# LB_BIT_1OUT-XL-v03_1_1x.net
KiCad netlist of a schematic drawn in EAGLE
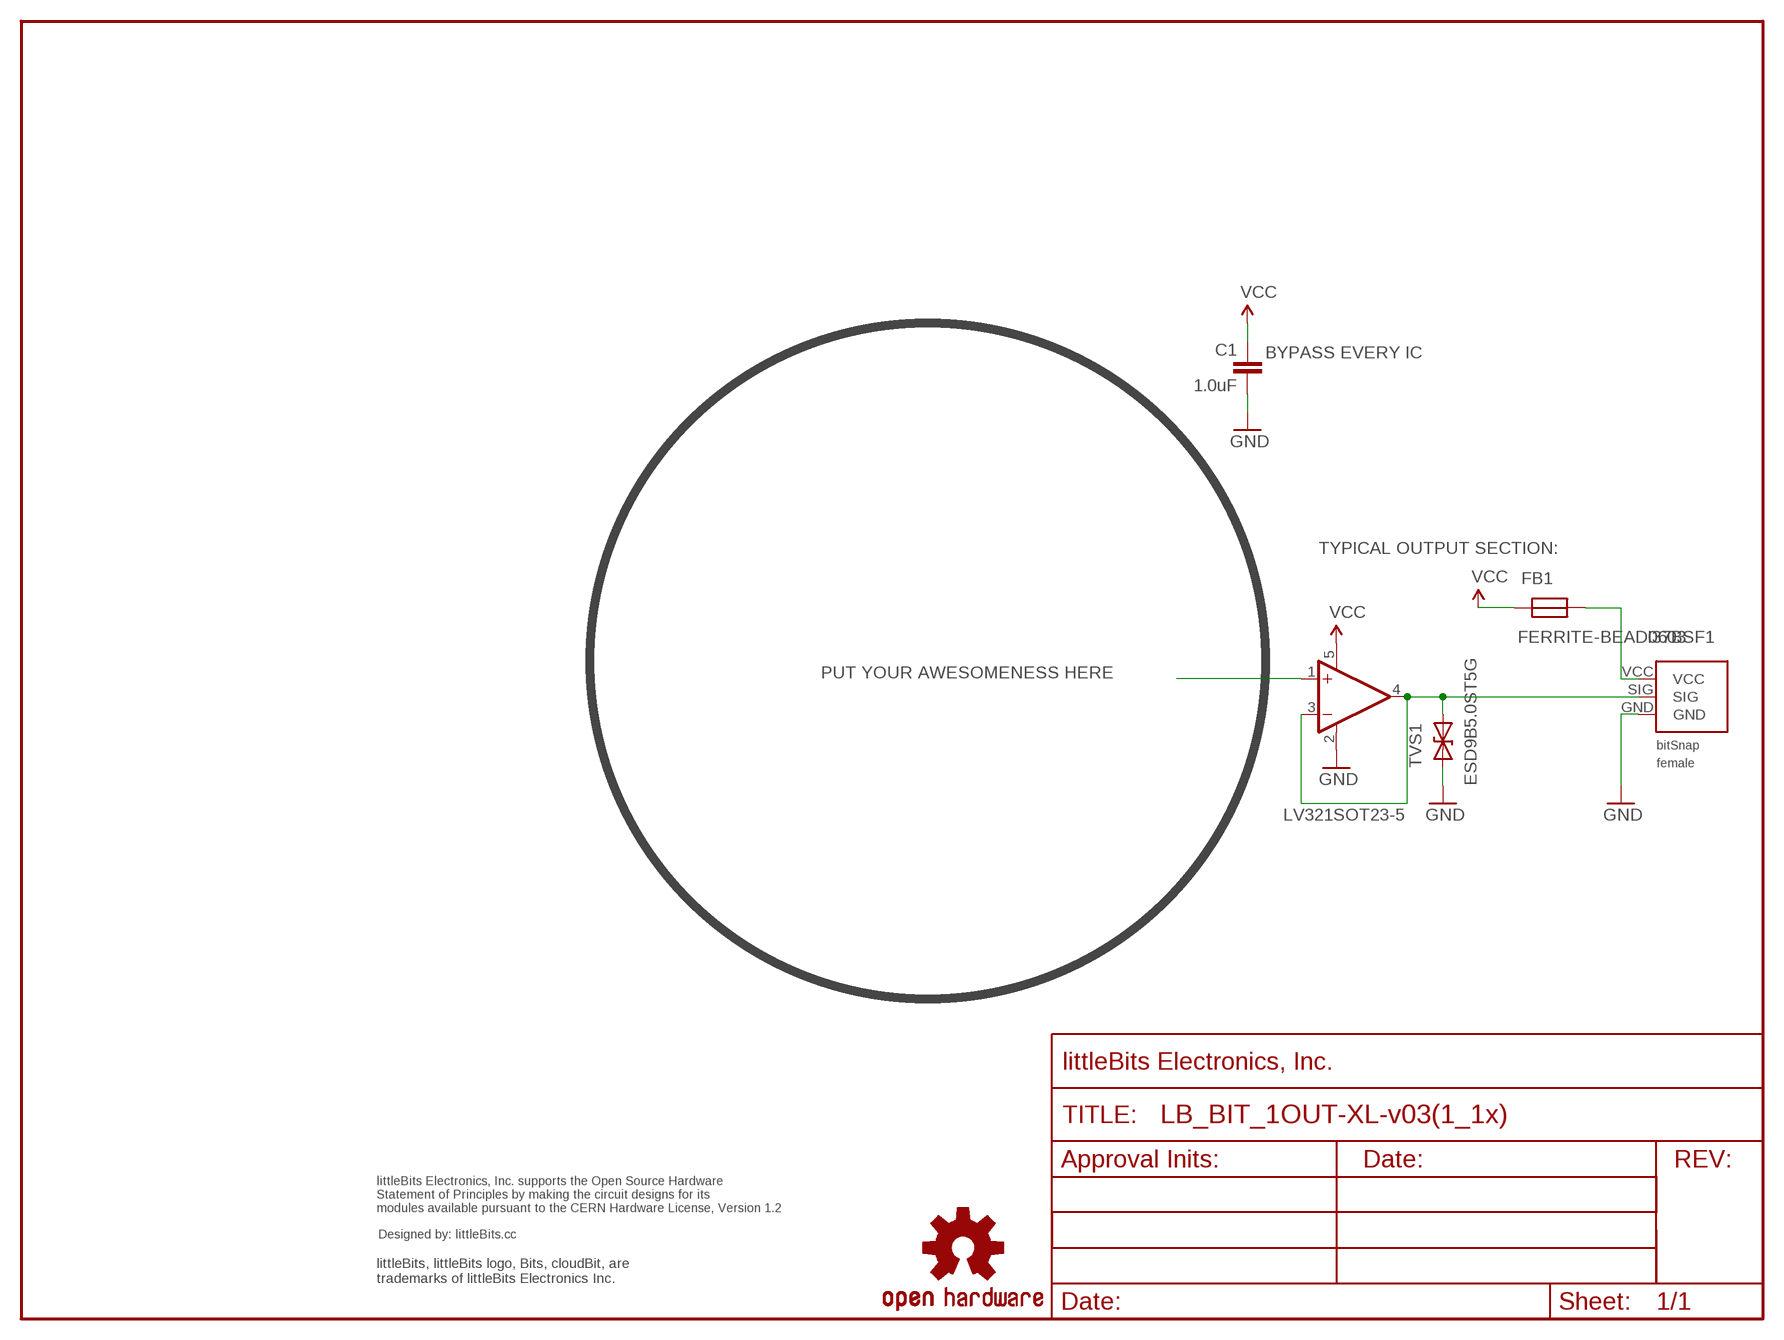
[diagram p0: schematic, sheet 1]

(export (version "E")
  (design (tool "Eeschema 10.0.6"))
  (components
    (comp (ref "C1")
      (value "1.0uF")
      (footprint "eagle-import:CAP-0603")
      (libsource (lib "eagle-import") (part "CAPCAP-0603"))
    )
    (comp (ref "FB1")
      (value "FERRITE-BEAD0603")
      (footprint "eagle-import:R0603")
      (libsource (lib "eagle-import") (part "FERRITE-BEAD0603"))
    )
    (comp (ref "FRAME1")
      (value "FRAME-LETTERWHITEMASK")
      (footprint "eagle-import:FABDWG01-WHITEMASK")
      (libsource (lib "eagle-import") (part "FRAME-LETTERWHITEMASK"))
    )
    (comp (ref "I37BSF1")
      (value "BITSNAP_V03_FEMALE")
      (footprint "eagle-import:BITSNAP_V03_FEMALE")
      (libsource (lib "eagle-import") (part "BITSNAP_V03_FEMALE"))
    )
    (comp (ref "TVS1")
      (value "ESD9B5.0ST5G")
      (footprint "eagle-import:SOD-923")
      (libsource (lib "eagle-import") (part "DIODE-TVSSOD-923"))
    )
    (comp (ref "U$1")
      (value "OSHWCREDIT")
      (footprint "eagle-import:OSHWCREDIT")
      (libsource (lib "eagle-import") (part "OSHWCREDIT"))
    )
    (comp (ref "U$3")
      (value "OSHW-LOGOL")
      (footprint "eagle-import:OSHW-LOGO-L")
      (libsource (lib "eagle-import") (part "OSHW-LOGOL"))
    )
    (comp (ref "U1")
      (value "LV321SOT23-5")
      (footprint "eagle-import:SOT23-5")
      (libsource (lib "eagle-import") (part "LV321SOT23-5"))
    )
  )
  (nets
    (net (code "1") (name "GND") (class "Default")
      (node (ref "C1") (pin "1") (pinfunction "1_1") (pintype "passive"))
      (node (ref "I37BSF1") (pin "GND") (pinfunction "GND_GND") (pintype "bidirectional"))
      (node (ref "TVS1") (pin "1") (pinfunction "A_1") (pintype "passive"))
      (node (ref "U1") (pin "2") (pinfunction "V-_2") (pintype "power_in"))
    )
    (net (code "2") (name "Net-(FB1-P$1)") (class "Default")
      (node (ref "FB1") (pin "1") (pinfunction "P$1_1") (pintype "bidirectional"))
      (node (ref "I37BSF1") (pin "VCC") (pinfunction "VCC_VCC") (pintype "bidirectional"))
    )
    (net (code "3") (name "Net-(TVS1-C)") (class "Default")
      (node (ref "I37BSF1") (pin "SIG") (pinfunction "SIG_SIG") (pintype "bidirectional"))
      (node (ref "TVS1") (pin "2") (pinfunction "C_2") (pintype "passive"))
      (node (ref "U1") (pin "3") (pinfunction "-IN_3") (pintype "input"))
      (node (ref "U1") (pin "4") (pinfunction "OUT_4") (pintype "output"))
    )
    (net (code "4") (name "VCC") (class "Default")
      (node (ref "C1") (pin "2") (pinfunction "2_2") (pintype "passive"))
      (node (ref "FB1") (pin "2") (pinfunction "P$2_2") (pintype "bidirectional"))
      (node (ref "U1") (pin "5") (pinfunction "V+_5") (pintype "power_in"))
    )
    (net (code "5") (name "unconnected-(U1-+IN-Pad1)") (class "Default")
      (node (ref "U1") (pin "1") (pinfunction "+IN_1") (pintype "input"))
    )
  )
)
